# Encoder.net
KiCad netlist of a schematic drawn in EAGLE
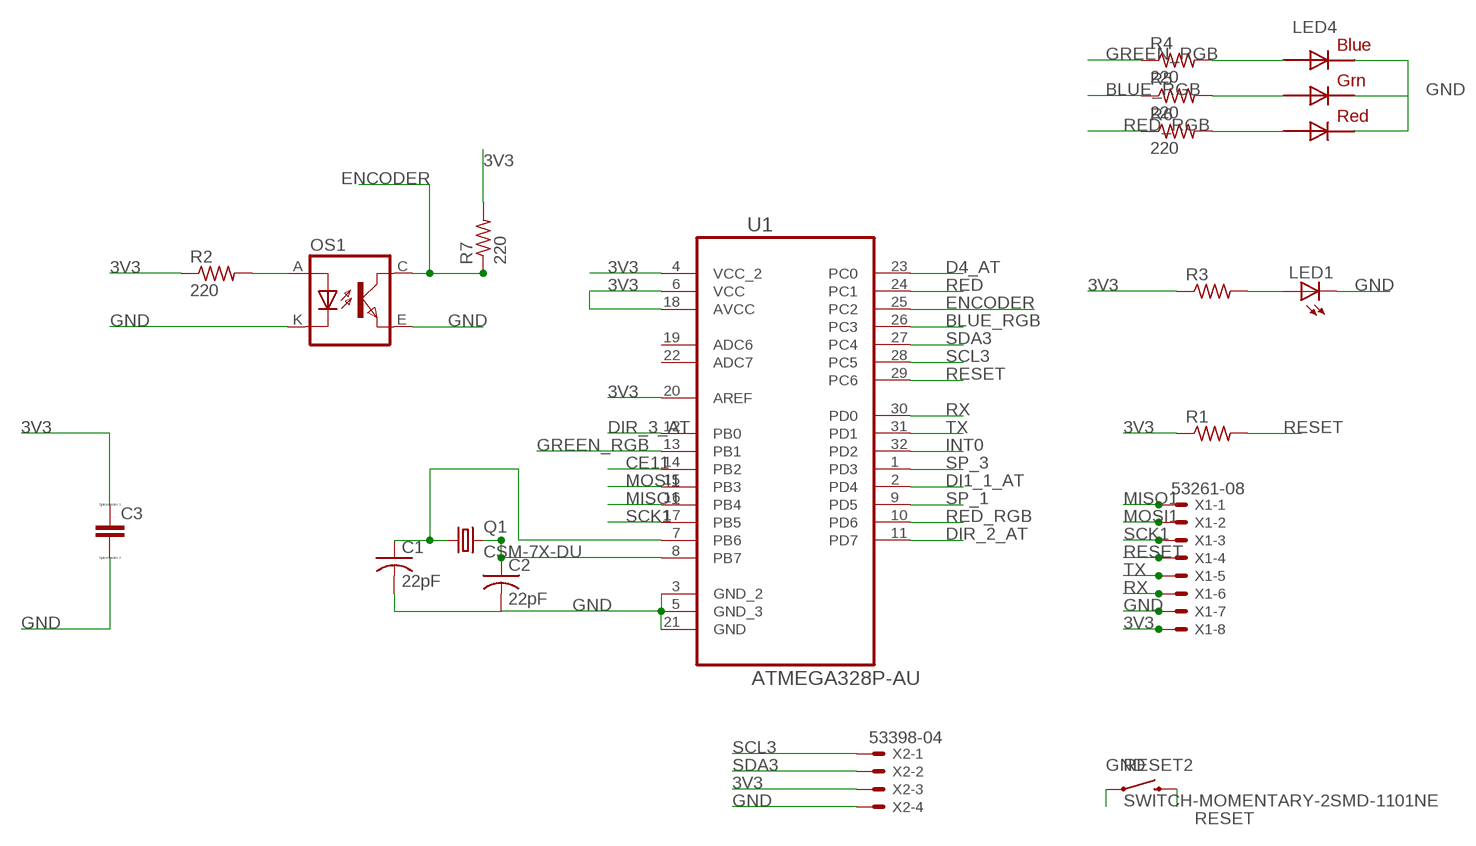
[diagram p0: schematic, sheet 1]

(export (version "E")
  (design (tool "Eeschema 10.0.6"))
  (components
    (comp (ref "C1")
      (value "22pF")
      (footprint "eagle-import:C0603")
      (libsource (lib "eagle-import") (part "C-USC0603"))
    )
    (comp (ref "C2")
      (value "22pF")
      (footprint "eagle-import:C0603")
      (libsource (lib "eagle-import") (part "C-USC0603"))
    )
    (comp (ref "C3")
      (value "CC1206")
      (footprint "eagle-import:C1206")
      (libsource (lib "eagle-import") (part "CC1206"))
    )
    (comp (ref "LED1")
      (value "LEDCHIPLED_1206")
      (footprint "eagle-import:CHIPLED_1206")
      (libsource (lib "eagle-import") (part "LEDCHIPLED_1206"))
    )
    (comp (ref "LED4")
      (value "RGBLED5050")
      (footprint "eagle-import:RGBLED5050")
      (libsource (lib "eagle-import") (part "RGBLED5050"))
    )
    (comp (ref "OS1")
      (value "TCRT5000")
      (footprint "eagle-import:TCRT5000")
      (libsource (lib "eagle-import") (part "TCRT5000"))
    )
    (comp (ref "Q1")
      (value "CSM-7X-DU")
      (footprint "eagle-import:CSM-7X-DU")
      (libsource (lib "eagle-import") (part "CSM-7X-DU"))
    )
    (comp (ref "R1")
      (value "R-US_M1206")
      (footprint "eagle-import:M1206")
      (libsource (lib "eagle-import") (part "R-US_M1206"))
    )
    (comp (ref "R2")
      (value "220")
      (footprint "eagle-import:R0603")
      (libsource (lib "eagle-import") (part "R-US_R0603"))
    )
    (comp (ref "R3")
      (value "R-US_M1206")
      (footprint "eagle-import:M1206")
      (libsource (lib "eagle-import") (part "R-US_M1206"))
    )
    (comp (ref "R4")
      (value "220")
      (footprint "eagle-import:R0603")
      (libsource (lib "eagle-import") (part "R-US_R0603"))
    )
    (comp (ref "R5")
      (value "220")
      (footprint "eagle-import:R0603")
      (libsource (lib "eagle-import") (part "R-US_R0603"))
    )
    (comp (ref "R6")
      (value "220")
      (footprint "eagle-import:R0603")
      (libsource (lib "eagle-import") (part "R-US_R0603"))
    )
    (comp (ref "R7")
      (value "220")
      (footprint "eagle-import:R0603")
      (libsource (lib "eagle-import") (part "R-US_R0603"))
    )
    (comp (ref "RESET2")
      (value "SWITCH-MOMENTARY-2SMD-1101NE")
      (footprint "eagle-import:TACTILE-SWITCH-1101NE")
      (libsource (lib "eagle-import") (part "SWITCH-MOMENTARY-2SMD-1101NE"))
    )
    (comp (ref "U1")
      (value "ATMEGA328P-AU")
      (footprint "eagle-import:QFP80P900X900X120-32N")
      (libsource (lib "eagle-import") (part "ATMEGA328P-AU"))
    )
    (comp (ref "X1")
      (value "53261-08")
      (footprint "eagle-import:53261-08")
      (fields (field (name "MF") "MOLEX"))
      (libsource (lib "eagle-import") (part "53?-08261"))
    )
    (comp (ref "X2")
      (value "53398-04")
      (footprint "eagle-import:53398-04")
      (fields (field (name "MF") "MOLEX"))
      (libsource (lib "eagle-import") (part "53?-04398"))
    )
  )
  (nets
    (net (code "1") (name "/3V3") (class "Default")
      (node (ref "C3") (pin "1") (pinfunction "1_1") (pintype "passive"))
      (node (ref "R1") (pin "1") (pinfunction "1_1") (pintype "passive"))
      (node (ref "R2") (pin "1") (pinfunction "1_1") (pintype "passive"))
      (node (ref "R3") (pin "1") (pinfunction "1_1") (pintype "passive"))
      (node (ref "R7") (pin "2") (pinfunction "2_2") (pintype "passive"))
      (node (ref "U1") (pin "18") (pinfunction "AVCC_18") (pintype "power_in"))
      (node (ref "U1") (pin "20") (pinfunction "AREF_20") (pintype "input"))
      (node (ref "U1") (pin "4") (pinfunction "VCC_2_4") (pintype "power_in"))
      (node (ref "U1") (pin "6") (pinfunction "VCC_6") (pintype "power_in"))
      (node (ref "X1") (pin "8") (pinfunction "S_8") (pintype "passive"))
      (node (ref "X2") (pin "3") (pinfunction "S_3") (pintype "passive"))
    )
    (net (code "2") (name "/BLUE_RGB") (class "Default")
      (node (ref "R5") (pin "1") (pinfunction "1_1") (pintype "passive"))
      (node (ref "U1") (pin "26") (pinfunction "PC3_26") (pintype "bidirectional"))
    )
    (net (code "3") (name "/CE11") (class "Default")
      (node (ref "U1") (pin "14") (pinfunction "PB2_14") (pintype "bidirectional"))
    )
    (net (code "4") (name "/D4_AT") (class "Default")
      (node (ref "U1") (pin "23") (pinfunction "PC0_23") (pintype "bidirectional"))
    )
    (net (code "5") (name "/DI1_1_AT") (class "Default")
      (node (ref "U1") (pin "2") (pinfunction "PD4_2") (pintype "bidirectional"))
    )
    (net (code "6") (name "/DIR_2_AT") (class "Default")
      (node (ref "U1") (pin "11") (pinfunction "PD7_11") (pintype "bidirectional"))
    )
    (net (code "7") (name "/DIR_3_AT") (class "Default")
      (node (ref "U1") (pin "12") (pinfunction "PB0_12") (pintype "bidirectional"))
    )
    (net (code "8") (name "/ENCODER") (class "Default")
      (node (ref "OS1") (pin "C") (pinfunction "COLLECTOR_C") (pintype "passive"))
      (node (ref "R7") (pin "1") (pinfunction "1_1") (pintype "passive"))
      (node (ref "U1") (pin "25") (pinfunction "PC2_25") (pintype "bidirectional"))
    )
    (net (code "9") (name "/GND") (class "Default")
      (node (ref "C1") (pin "2") (pinfunction "2_2") (pintype "passive"))
      (node (ref "C2") (pin "2") (pinfunction "2_2") (pintype "passive"))
      (node (ref "C3") (pin "2") (pinfunction "2_2") (pintype "passive"))
      (node (ref "LED1") (pin "C") (pinfunction "C_C") (pintype "passive"))
      (node (ref "LED4") (pin "4") (pinfunction "BLUE_C_4") (pintype "bidirectional"))
      (node (ref "LED4") (pin "5") (pinfunction "RED_C_5") (pintype "bidirectional"))
      (node (ref "LED4") (pin "6") (pinfunction "GREEN_C_6") (pintype "bidirectional"))
      (node (ref "OS1") (pin "E") (pinfunction "EMITTER_E") (pintype "passive"))
      (node (ref "OS1") (pin "K") (pinfunction "CATHODE_K") (pintype "passive"))
      (node (ref "RESET2") (pin "1") (pinfunction "1_1") (pintype "passive"))
      (node (ref "U1") (pin "21") (pinfunction "GND_21") (pintype "passive"))
      (node (ref "U1") (pin "3") (pinfunction "GND_2_3") (pintype "passive"))
      (node (ref "U1") (pin "5") (pinfunction "GND_3_5") (pintype "passive"))
      (node (ref "X1") (pin "7") (pinfunction "S_7") (pintype "passive"))
      (node (ref "X2") (pin "4") (pinfunction "S_4") (pintype "passive"))
    )
    (net (code "10") (name "/GREEN_RGB") (class "Default")
      (node (ref "R4") (pin "1") (pinfunction "1_1") (pintype "passive"))
      (node (ref "U1") (pin "13") (pinfunction "PB1_13") (pintype "bidirectional"))
    )
    (net (code "11") (name "/INT0") (class "Default")
      (node (ref "U1") (pin "32") (pinfunction "PD2_32") (pintype "bidirectional"))
    )
    (net (code "12") (name "/MISO1") (class "Default")
      (node (ref "U1") (pin "16") (pinfunction "PB4_16") (pintype "bidirectional"))
      (node (ref "X1") (pin "1") (pinfunction "S_1") (pintype "passive"))
    )
    (net (code "13") (name "/MOSI1") (class "Default")
      (node (ref "U1") (pin "15") (pinfunction "PB3_15") (pintype "bidirectional"))
      (node (ref "X1") (pin "2") (pinfunction "S_2") (pintype "passive"))
    )
    (net (code "14") (name "/RED") (class "Default")
      (node (ref "U1") (pin "24") (pinfunction "PC1_24") (pintype "bidirectional"))
    )
    (net (code "15") (name "/RED_RGB") (class "Default")
      (node (ref "R6") (pin "1") (pinfunction "1_1") (pintype "passive"))
      (node (ref "U1") (pin "10") (pinfunction "PD6_10") (pintype "bidirectional"))
    )
    (net (code "16") (name "/RESET") (class "Default")
      (node (ref "R1") (pin "2") (pinfunction "2_2") (pintype "passive"))
      (node (ref "RESET2") (pin "2") (pinfunction "2_2") (pintype "passive"))
      (node (ref "U1") (pin "29") (pinfunction "PC6_29") (pintype "bidirectional"))
      (node (ref "X1") (pin "4") (pinfunction "S_4") (pintype "passive"))
    )
    (net (code "17") (name "/RX") (class "Default")
      (node (ref "U1") (pin "30") (pinfunction "PD0_30") (pintype "bidirectional"))
      (node (ref "X1") (pin "6") (pinfunction "S_6") (pintype "passive"))
    )
    (net (code "18") (name "/SCK1") (class "Default")
      (node (ref "U1") (pin "17") (pinfunction "PB5_17") (pintype "bidirectional"))
      (node (ref "X1") (pin "3") (pinfunction "S_3") (pintype "passive"))
    )
    (net (code "19") (name "/SCL3") (class "Default")
      (node (ref "U1") (pin "28") (pinfunction "PC5_28") (pintype "bidirectional"))
      (node (ref "X2") (pin "1") (pinfunction "S_1") (pintype "passive"))
    )
    (net (code "20") (name "/SDA3") (class "Default")
      (node (ref "U1") (pin "27") (pinfunction "PC4_27") (pintype "bidirectional"))
      (node (ref "X2") (pin "2") (pinfunction "S_2") (pintype "passive"))
    )
    (net (code "21") (name "/SP_1") (class "Default")
      (node (ref "U1") (pin "9") (pinfunction "PD5_9") (pintype "bidirectional"))
    )
    (net (code "22") (name "/SP_3") (class "Default")
      (node (ref "U1") (pin "1") (pinfunction "PD3_1") (pintype "bidirectional"))
    )
    (net (code "23") (name "/TX") (class "Default")
      (node (ref "U1") (pin "31") (pinfunction "PD1_31") (pintype "bidirectional"))
      (node (ref "X1") (pin "5") (pinfunction "S_5") (pintype "passive"))
    )
    (net (code "24") (name "Net-(LED1-PadA)") (class "Default")
      (node (ref "LED1") (pin "A") (pinfunction "A_A") (pintype "passive"))
      (node (ref "R3") (pin "2") (pinfunction "2_2") (pintype "passive"))
    )
    (net (code "25") (name "Net-(LED4-BLUE_A)") (class "Default")
      (node (ref "LED4") (pin "3") (pinfunction "BLUE_A_3") (pintype "bidirectional"))
      (node (ref "R4") (pin "2") (pinfunction "2_2") (pintype "passive"))
    )
    (net (code "26") (name "Net-(LED4-GREEN_A)") (class "Default")
      (node (ref "LED4") (pin "1") (pinfunction "GREEN_A_1") (pintype "bidirectional"))
      (node (ref "R5") (pin "2") (pinfunction "2_2") (pintype "passive"))
    )
    (net (code "27") (name "Net-(LED4-RED_A)") (class "Default")
      (node (ref "LED4") (pin "2") (pinfunction "RED_A_2") (pintype "bidirectional"))
      (node (ref "R6") (pin "2") (pinfunction "2_2") (pintype "passive"))
    )
    (net (code "28") (name "Net-(OS1-ANODE)") (class "Default")
      (node (ref "OS1") (pin "A") (pinfunction "ANODE_A") (pintype "passive"))
      (node (ref "R2") (pin "2") (pinfunction "2_2") (pintype "passive"))
    )
    (net (code "29") (name "Net-(U1-PB6)") (class "Default")
      (node (ref "C1") (pin "1") (pinfunction "1_1") (pintype "passive"))
      (node (ref "Q1") (pin "1") (pinfunction "1_1") (pintype "passive"))
      (node (ref "U1") (pin "7") (pinfunction "PB6_7") (pintype "bidirectional"))
    )
    (net (code "30") (name "Net-(U1-PB7)") (class "Default")
      (node (ref "C2") (pin "1") (pinfunction "1_1") (pintype "passive"))
      (node (ref "Q1") (pin "2") (pinfunction "2_2") (pintype "passive"))
      (node (ref "U1") (pin "8") (pinfunction "PB7_8") (pintype "bidirectional"))
    )
    (net (code "31") (name "unconnected-(U1-ADC6-Pad19)") (class "Default")
      (node (ref "U1") (pin "19") (pinfunction "ADC6_19") (pintype "input"))
    )
    (net (code "32") (name "unconnected-(U1-ADC7-Pad22)") (class "Default")
      (node (ref "U1") (pin "22") (pinfunction "ADC7_22") (pintype "input"))
    )
  )
)
